# m_tes_expander.net
KiCad netlist of a schematic drawn in EAGLE
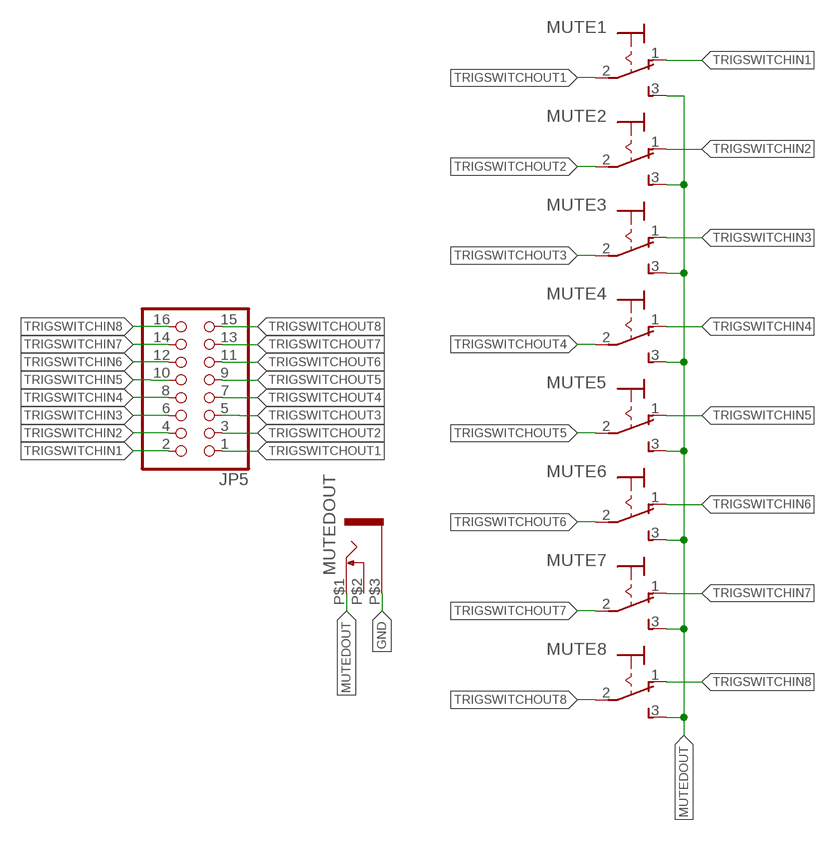
[diagram p0: schematic, sheet 1]

(export (version "E")
  (design (tool "Eeschema 10.0.6"))
  (components
    (comp (ref "JP5")
      (value "PINHD-2X8")
      (footprint "eagle-import:2X08")
      (libsource (lib "eagle-import") (part "PINHD-2X8"))
    )
    (comp (ref "MUTE1")
      (value "320-916320-916BIG")
      (footprint "eagle-import:320-916MY")
      (libsource (lib "eagle-import") (part "320-916320-916BIG"))
    )
    (comp (ref "MUTE2")
      (value "320-916320-916BIG")
      (footprint "eagle-import:320-916MY")
      (libsource (lib "eagle-import") (part "320-916320-916BIG"))
    )
    (comp (ref "MUTE3")
      (value "320-916320-916BIG")
      (footprint "eagle-import:320-916MY")
      (libsource (lib "eagle-import") (part "320-916320-916BIG"))
    )
    (comp (ref "MUTE4")
      (value "320-916320-916BIG")
      (footprint "eagle-import:320-916MY")
      (libsource (lib "eagle-import") (part "320-916320-916BIG"))
    )
    (comp (ref "MUTE5")
      (value "320-916320-916BIG")
      (footprint "eagle-import:320-916MY")
      (libsource (lib "eagle-import") (part "320-916320-916BIG"))
    )
    (comp (ref "MUTE6")
      (value "320-916320-916BIG")
      (footprint "eagle-import:320-916MY")
      (libsource (lib "eagle-import") (part "320-916320-916BIG"))
    )
    (comp (ref "MUTE7")
      (value "320-916320-916BIG")
      (footprint "eagle-import:320-916MY")
      (libsource (lib "eagle-import") (part "320-916320-916BIG"))
    )
    (comp (ref "MUTE8")
      (value "320-916320-916BIG")
      (footprint "eagle-import:320-916MY")
      (libsource (lib "eagle-import") (part "320-916320-916BIG"))
    )
    (comp (ref "MUTEDOUT")
      (value "WQP-PJ301M-12_JACK")
      (footprint "eagle-import:WQP-PJ301M-12_JACK")
      (libsource (lib "eagle-import") (part "WQP-PJ301M-12_JACK"))
    )
  )
  (nets
    (net (code "1") (name "GND") (class "Default")
      (node (ref "MUTEDOUT") (pin "P$3") (pinfunction "1_P$3") (pintype "passive"))
    )
    (net (code "2") (name "MUTEDOUT") (class "Default")
      (node (ref "MUTE1") (pin "3") (pinfunction "S_3") (pintype "passive"))
      (node (ref "MUTE2") (pin "3") (pinfunction "S_3") (pintype "passive"))
      (node (ref "MUTE3") (pin "3") (pinfunction "S_3") (pintype "passive"))
      (node (ref "MUTE4") (pin "3") (pinfunction "S_3") (pintype "passive"))
      (node (ref "MUTE5") (pin "3") (pinfunction "S_3") (pintype "passive"))
      (node (ref "MUTE6") (pin "3") (pinfunction "S_3") (pintype "passive"))
      (node (ref "MUTE7") (pin "3") (pinfunction "S_3") (pintype "passive"))
      (node (ref "MUTE8") (pin "3") (pinfunction "S_3") (pintype "passive"))
      (node (ref "MUTEDOUT") (pin "P$1") (pinfunction "2_P$1") (pintype "passive"))
    )
    (net (code "3") (name "TRIGSWITCHIN1") (class "Default")
      (node (ref "JP5") (pin "2") (pinfunction "2_2") (pintype "passive"))
      (node (ref "MUTE1") (pin "1") (pinfunction "O_1") (pintype "passive"))
    )
    (net (code "4") (name "TRIGSWITCHIN2") (class "Default")
      (node (ref "JP5") (pin "4") (pinfunction "4_4") (pintype "passive"))
      (node (ref "MUTE2") (pin "1") (pinfunction "O_1") (pintype "passive"))
    )
    (net (code "5") (name "TRIGSWITCHIN3") (class "Default")
      (node (ref "JP5") (pin "6") (pinfunction "6_6") (pintype "passive"))
      (node (ref "MUTE3") (pin "1") (pinfunction "O_1") (pintype "passive"))
    )
    (net (code "6") (name "TRIGSWITCHIN4") (class "Default")
      (node (ref "JP5") (pin "8") (pinfunction "8_8") (pintype "passive"))
      (node (ref "MUTE4") (pin "1") (pinfunction "O_1") (pintype "passive"))
    )
    (net (code "7") (name "TRIGSWITCHIN5") (class "Default")
      (node (ref "JP5") (pin "10") (pinfunction "10_10") (pintype "passive"))
      (node (ref "MUTE5") (pin "1") (pinfunction "O_1") (pintype "passive"))
    )
    (net (code "8") (name "TRIGSWITCHIN6") (class "Default")
      (node (ref "JP5") (pin "12") (pinfunction "12_12") (pintype "passive"))
      (node (ref "MUTE6") (pin "1") (pinfunction "O_1") (pintype "passive"))
    )
    (net (code "9") (name "TRIGSWITCHIN7") (class "Default")
      (node (ref "JP5") (pin "14") (pinfunction "14_14") (pintype "passive"))
      (node (ref "MUTE7") (pin "1") (pinfunction "O_1") (pintype "passive"))
    )
    (net (code "10") (name "TRIGSWITCHIN8") (class "Default")
      (node (ref "JP5") (pin "16") (pinfunction "16_16") (pintype "passive"))
      (node (ref "MUTE8") (pin "1") (pinfunction "O_1") (pintype "passive"))
    )
    (net (code "11") (name "TRIGSWITCHOUT1") (class "Default")
      (node (ref "JP5") (pin "1") (pinfunction "1_1") (pintype "passive"))
      (node (ref "MUTE1") (pin "2") (pinfunction "P_2") (pintype "passive"))
    )
    (net (code "12") (name "TRIGSWITCHOUT2") (class "Default")
      (node (ref "JP5") (pin "3") (pinfunction "3_3") (pintype "passive"))
      (node (ref "MUTE2") (pin "2") (pinfunction "P_2") (pintype "passive"))
    )
    (net (code "13") (name "TRIGSWITCHOUT3") (class "Default")
      (node (ref "JP5") (pin "5") (pinfunction "5_5") (pintype "passive"))
      (node (ref "MUTE3") (pin "2") (pinfunction "P_2") (pintype "passive"))
    )
    (net (code "14") (name "TRIGSWITCHOUT4") (class "Default")
      (node (ref "JP5") (pin "7") (pinfunction "7_7") (pintype "passive"))
      (node (ref "MUTE4") (pin "2") (pinfunction "P_2") (pintype "passive"))
    )
    (net (code "15") (name "TRIGSWITCHOUT5") (class "Default")
      (node (ref "JP5") (pin "9") (pinfunction "9_9") (pintype "passive"))
      (node (ref "MUTE5") (pin "2") (pinfunction "P_2") (pintype "passive"))
    )
    (net (code "16") (name "TRIGSWITCHOUT6") (class "Default")
      (node (ref "JP5") (pin "11") (pinfunction "11_11") (pintype "passive"))
      (node (ref "MUTE6") (pin "2") (pinfunction "P_2") (pintype "passive"))
    )
    (net (code "17") (name "TRIGSWITCHOUT7") (class "Default")
      (node (ref "JP5") (pin "13") (pinfunction "13_13") (pintype "passive"))
      (node (ref "MUTE7") (pin "2") (pinfunction "P_2") (pintype "passive"))
    )
    (net (code "18") (name "TRIGSWITCHOUT8") (class "Default")
      (node (ref "JP5") (pin "15") (pinfunction "15_15") (pintype "passive"))
      (node (ref "MUTE8") (pin "2") (pinfunction "P_2") (pintype "passive"))
    )
    (net (code "19") (name "unconnected-(MUTEDOUT-3-PadP$2)") (class "Default")
      (node (ref "MUTEDOUT") (pin "P$2") (pinfunction "3_P$2") (pintype "passive"))
    )
  )
)
